# spi_mit_sram_v1.net
KiCad netlist of a schematic drawn in EAGLE
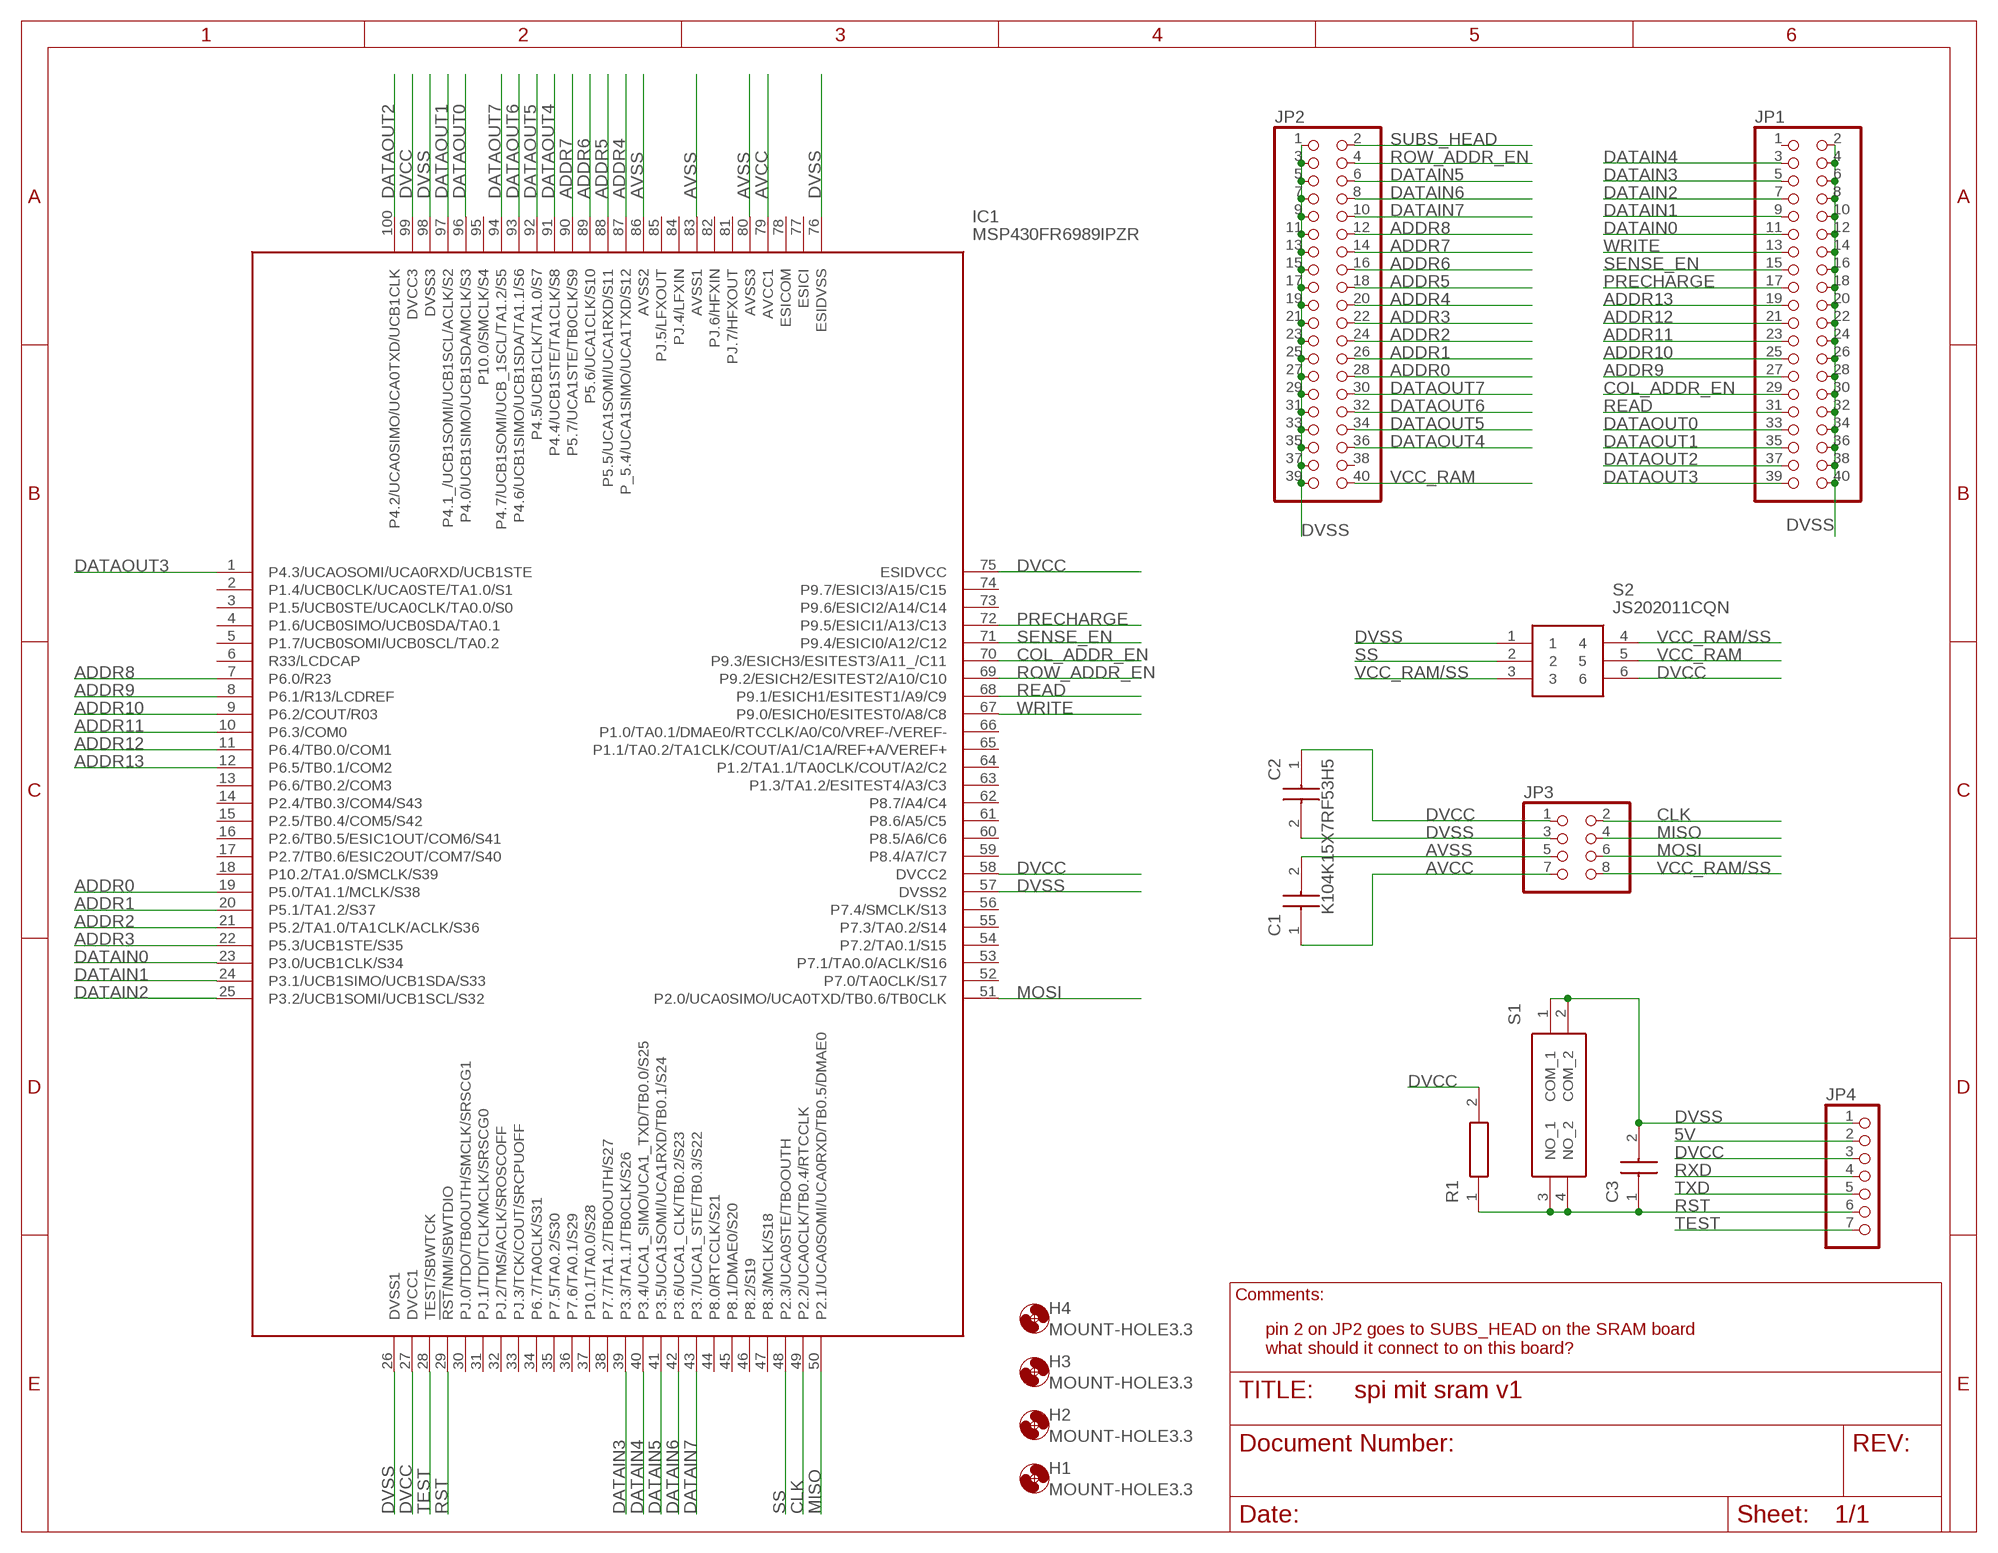
[diagram p0: schematic, sheet 1]

(export (version "E")
  (design (tool "Eeschema 10.0.6"))
  (components
    (comp (ref "C1")
      (value "K104K15X7RF53H5")
      (footprint "eagle-import:K104K15X7RF53H5")
      (fields
        (field (name "MOUSER_PART_NUMBER") "594-K104K15X7RF53H5")
        (field (name "RS_PART_NUMBER") "8523270")
      )
      (libsource (lib "eagle-import") (part "K104K15X7RF53H5"))
    )
    (comp (ref "C2")
      (value "K104K15X7RF53H5")
      (footprint "eagle-import:K104K15X7RF53H5")
      (fields
        (field (name "MOUSER_PART_NUMBER") "594-K104K15X7RF53H5")
        (field (name "RS_PART_NUMBER") "8523270")
      )
      (libsource (lib "eagle-import") (part "K104K15X7RF53H5"))
    )
    (comp (ref "C3")
      (value "K104K15X7RF53H5")
      (footprint "eagle-import:K104K15X7RF53H5")
      (fields
        (field (name "MOUSER_PART_NUMBER") "594-K104K15X7RF53H5")
        (field (name "RS_PART_NUMBER") "8523270")
      )
      (libsource (lib "eagle-import") (part "K104K15X7RF53H5"))
    )
    (comp (ref "H1")
      (value "MOUNT-HOLE3.3")
      (footprint "eagle-import:3,3")
      (libsource (lib "eagle-import") (part "MOUNT-HOLE3.3"))
    )
    (comp (ref "H2")
      (value "MOUNT-HOLE3.3")
      (footprint "eagle-import:3,3")
      (libsource (lib "eagle-import") (part "MOUNT-HOLE3.3"))
    )
    (comp (ref "H3")
      (value "MOUNT-HOLE3.3")
      (footprint "eagle-import:3,3")
      (libsource (lib "eagle-import") (part "MOUNT-HOLE3.3"))
    )
    (comp (ref "H4")
      (value "MOUNT-HOLE3.3")
      (footprint "eagle-import:3,3")
      (libsource (lib "eagle-import") (part "MOUNT-HOLE3.3"))
    )
    (comp (ref "IC1")
      (value "MSP430FR6989IPZR")
      (footprint "eagle-import:QFP50P1600X1600X160-100N")
      (fields (field (name "MOUSER_PART_NUMBER") "595-MSP430FR6989IPZR"))
      (libsource (lib "eagle-import") (part "MSP430FR6989IPZR"))
    )
    (comp (ref "JP1")
      (value "PINHD-2X20")
      (footprint "eagle-import:2X20")
      (libsource (lib "eagle-import") (part "PINHD-2X20"))
    )
    (comp (ref "JP2")
      (value "PINHD-2X20")
      (footprint "eagle-import:2X20")
      (libsource (lib "eagle-import") (part "PINHD-2X20"))
    )
    (comp (ref "JP3")
      (value "PINHD-2X4")
      (footprint "eagle-import:2X04")
      (libsource (lib "eagle-import") (part "PINHD-2X4"))
    )
    (comp (ref "JP4")
      (value "PINHD-1X7")
      (footprint "eagle-import:1X07")
      (libsource (lib "eagle-import") (part "PINHD-1X7"))
    )
    (comp (ref "R1")
      (value "MF0207FTE52-10K")
      (footprint "eagle-import:RESAD1590W60L630D240")
      (fields (field (name "MOUSER_PART_NUMBER") "603-MF0207FTE52-10K"))
      (libsource (lib "eagle-import") (part "MF0207FTE52-10K"))
    )
    (comp (ref "S1")
      (value "1825910-3")
      (footprint "eagle-import:18259103")
      (fields (field (name "RS_PART_NUMBER") "7455817P"))
      (libsource (lib "eagle-import") (part "1825910-3"))
    )
    (comp (ref "S2")
      (value "JS202011CQN")
      (footprint "eagle-import:JS202011CQN")
      (fields (field (name "MOUSER_PART_NUMBER") "611-JS202011CQN") (field (name "RS_PART_NUMBER") "1546136"))
      (libsource (lib "eagle-import") (part "JS202011CQN"))
    )
  )
  (nets
    (net (code "1") (name "/5V") (class "Default")
      (node (ref "JP4") (pin "2") (pinfunction "2_2") (pintype "passive"))
    )
    (net (code "2") (name "/ADDR0") (class "Default")
      (node (ref "IC1") (pin "19") (pinfunction "P5.0/TA1.1/MCLK/S38_19") (pintype "bidirectional"))
      (node (ref "JP2") (pin "28") (pinfunction "28_28") (pintype "passive"))
    )
    (net (code "3") (name "/ADDR1") (class "Default")
      (node (ref "IC1") (pin "20") (pinfunction "P5.1/TA1.2/S37_20") (pintype "bidirectional"))
      (node (ref "JP2") (pin "26") (pinfunction "26_26") (pintype "passive"))
    )
    (net (code "4") (name "/ADDR2") (class "Default")
      (node (ref "IC1") (pin "21") (pinfunction "P5.2/TA1.0/TA1CLK/ACLK/S36_21") (pintype "bidirectional"))
      (node (ref "JP2") (pin "24") (pinfunction "24_24") (pintype "passive"))
    )
    (net (code "5") (name "/ADDR3") (class "Default")
      (node (ref "IC1") (pin "22") (pinfunction "P5.3/UCB1STE/S35_22") (pintype "bidirectional"))
      (node (ref "JP2") (pin "22") (pinfunction "22_22") (pintype "passive"))
    )
    (net (code "6") (name "/ADDR4") (class "Default")
      (node (ref "IC1") (pin "87") (pinfunction "P_5.4/UCA1SIMO/UCA1TXD/S12_87") (pintype "bidirectional"))
      (node (ref "JP2") (pin "20") (pinfunction "20_20") (pintype "passive"))
    )
    (net (code "7") (name "/ADDR5") (class "Default")
      (node (ref "IC1") (pin "88") (pinfunction "P5.5/UCA1SOMI/UCA1RXD/S11_88") (pintype "bidirectional"))
      (node (ref "JP2") (pin "18") (pinfunction "18_18") (pintype "passive"))
    )
    (net (code "8") (name "/ADDR6") (class "Default")
      (node (ref "IC1") (pin "89") (pinfunction "P5.6/UCA1CLK/S10_89") (pintype "bidirectional"))
      (node (ref "JP2") (pin "16") (pinfunction "16_16") (pintype "passive"))
    )
    (net (code "9") (name "/ADDR7") (class "Default")
      (node (ref "IC1") (pin "90") (pinfunction "P5.7/UCA1STE/TB0CLK/S9_90") (pintype "bidirectional"))
      (node (ref "JP2") (pin "14") (pinfunction "14_14") (pintype "passive"))
    )
    (net (code "10") (name "/ADDR8") (class "Default")
      (node (ref "IC1") (pin "7") (pinfunction "P6.0/R23_7") (pintype "bidirectional"))
      (node (ref "JP2") (pin "12") (pinfunction "12_12") (pintype "passive"))
    )
    (net (code "11") (name "/ADDR9") (class "Default")
      (node (ref "IC1") (pin "8") (pinfunction "P6.1/R13/LCDREF_8") (pintype "bidirectional"))
      (node (ref "JP1") (pin "27") (pinfunction "27_27") (pintype "passive"))
    )
    (net (code "12") (name "/ADDR10") (class "Default")
      (node (ref "IC1") (pin "9") (pinfunction "P6.2/COUT/R03_9") (pintype "bidirectional"))
      (node (ref "JP1") (pin "25") (pinfunction "25_25") (pintype "passive"))
    )
    (net (code "13") (name "/ADDR11") (class "Default")
      (node (ref "IC1") (pin "10") (pinfunction "P6.3/COM0_10") (pintype "bidirectional"))
      (node (ref "JP1") (pin "23") (pinfunction "23_23") (pintype "passive"))
    )
    (net (code "14") (name "/ADDR12") (class "Default")
      (node (ref "IC1") (pin "11") (pinfunction "P6.4/TB0.0/COM1_11") (pintype "bidirectional"))
      (node (ref "JP1") (pin "21") (pinfunction "21_21") (pintype "passive"))
    )
    (net (code "15") (name "/ADDR13") (class "Default")
      (node (ref "IC1") (pin "12") (pinfunction "P6.5/TB0.1/COM2_12") (pintype "bidirectional"))
      (node (ref "JP1") (pin "19") (pinfunction "19_19") (pintype "passive"))
    )
    (net (code "16") (name "/AVCC") (class "Default")
      (node (ref "C1") (pin "1") (pinfunction "1_1") (pintype "bidirectional"))
      (node (ref "IC1") (pin "79") (pinfunction "AVCC1_79") (pintype "bidirectional"))
      (node (ref "JP3") (pin "7") (pinfunction "7_7") (pintype "passive"))
    )
    (net (code "17") (name "/AVSS") (class "Default")
      (node (ref "C1") (pin "2") (pinfunction "2_2") (pintype "bidirectional"))
      (node (ref "IC1") (pin "80") (pinfunction "AVSS3_80") (pintype "bidirectional"))
      (node (ref "IC1") (pin "83") (pinfunction "AVSS1_83") (pintype "bidirectional"))
      (node (ref "IC1") (pin "86") (pinfunction "AVSS2_86") (pintype "bidirectional"))
      (node (ref "JP3") (pin "5") (pinfunction "5_5") (pintype "passive"))
    )
    (net (code "18") (name "/CLK") (class "Default")
      (node (ref "IC1") (pin "49") (pinfunction "P2.2/UCA0CLK/TB0.4/RTCCLK_49") (pintype "bidirectional"))
      (node (ref "JP3") (pin "2") (pinfunction "2_2") (pintype "passive"))
    )
    (net (code "19") (name "/COL_ADDR_EN") (class "Default")
      (node (ref "IC1") (pin "70") (pinfunction "P9.3/ESICH3/ESITEST3/A11_/C11_70") (pintype "bidirectional"))
      (node (ref "JP1") (pin "29") (pinfunction "29_29") (pintype "passive"))
    )
    (net (code "20") (name "/DATAIN0") (class "Default")
      (node (ref "IC1") (pin "23") (pinfunction "P3.0/UCB1CLK/S34_23") (pintype "bidirectional"))
      (node (ref "JP1") (pin "11") (pinfunction "11_11") (pintype "passive"))
    )
    (net (code "21") (name "/DATAIN1") (class "Default")
      (node (ref "IC1") (pin "24") (pinfunction "P3.1/UCB1SIMO/UCB1SDA/S33_24") (pintype "bidirectional"))
      (node (ref "JP1") (pin "9") (pinfunction "9_9") (pintype "passive"))
    )
    (net (code "22") (name "/DATAIN2") (class "Default")
      (node (ref "IC1") (pin "25") (pinfunction "P3.2/UCB1SOMI/UCB1SCL/S32_25") (pintype "bidirectional"))
      (node (ref "JP1") (pin "7") (pinfunction "7_7") (pintype "passive"))
    )
    (net (code "23") (name "/DATAIN3") (class "Default")
      (node (ref "IC1") (pin "39") (pinfunction "P3.3/TA1.1/TB0CLK/S26_39") (pintype "bidirectional"))
      (node (ref "JP1") (pin "5") (pinfunction "5_5") (pintype "passive"))
    )
    (net (code "24") (name "/DATAIN4") (class "Default")
      (node (ref "IC1") (pin "40") (pinfunction "P3.4/UCA1_SIMO/UCA1_TXD/TB0.0/S25_40") (pintype "bidirectional"))
      (node (ref "JP1") (pin "3") (pinfunction "3_3") (pintype "passive"))
    )
    (net (code "25") (name "/DATAIN5") (class "Default")
      (node (ref "IC1") (pin "41") (pinfunction "P3.5/UCA1SOMI/UCA1RXD/TB0.1/S24_41") (pintype "bidirectional"))
      (node (ref "JP2") (pin "6") (pinfunction "6_6") (pintype "passive"))
    )
    (net (code "26") (name "/DATAIN6") (class "Default")
      (node (ref "IC1") (pin "42") (pinfunction "P3.6/UCA1_CLK/TB0.2/S23_42") (pintype "bidirectional"))
      (node (ref "JP2") (pin "8") (pinfunction "8_8") (pintype "passive"))
    )
    (net (code "27") (name "/DATAIN7") (class "Default")
      (node (ref "IC1") (pin "43") (pinfunction "P3.7/UCA1_STE/TB0.3/S22_43") (pintype "bidirectional"))
      (node (ref "JP2") (pin "10") (pinfunction "10_10") (pintype "passive"))
    )
    (net (code "28") (name "/DATAOUT0") (class "Default")
      (node (ref "IC1") (pin "96") (pinfunction "P4.0/UCB1SIMO/UCB1SDA/MCLK/S3_96") (pintype "bidirectional"))
      (node (ref "JP1") (pin "33") (pinfunction "33_33") (pintype "passive"))
    )
    (net (code "29") (name "/DATAOUT1") (class "Default")
      (node (ref "IC1") (pin "97") (pinfunction "P4.1_/UCB1SOMI/UCB1SCL/ACLK/S2_97") (pintype "bidirectional"))
      (node (ref "JP1") (pin "35") (pinfunction "35_35") (pintype "passive"))
    )
    (net (code "30") (name "/DATAOUT2") (class "Default")
      (node (ref "IC1") (pin "100") (pinfunction "P4.2/UCA0SIMO/UCA0TXD/UCB1CLK_100") (pintype "bidirectional"))
      (node (ref "JP1") (pin "37") (pinfunction "37_37") (pintype "passive"))
    )
    (net (code "31") (name "/DATAOUT3") (class "Default")
      (node (ref "IC1") (pin "1") (pinfunction "P4.3/UCAOSOMI/UCA0RXD/UCB1STE_1") (pintype "bidirectional"))
      (node (ref "JP1") (pin "39") (pinfunction "39_39") (pintype "passive"))
    )
    (net (code "32") (name "/DATAOUT4") (class "Default")
      (node (ref "IC1") (pin "91") (pinfunction "P4.4/UCB1STE/TA1CLK/S8_91") (pintype "bidirectional"))
      (node (ref "JP2") (pin "36") (pinfunction "36_36") (pintype "passive"))
    )
    (net (code "33") (name "/DATAOUT5") (class "Default")
      (node (ref "IC1") (pin "92") (pinfunction "P4.5/UCB1CLK/TA1.0/S7_92") (pintype "bidirectional"))
      (node (ref "JP2") (pin "34") (pinfunction "34_34") (pintype "passive"))
    )
    (net (code "34") (name "/DATAOUT6") (class "Default")
      (node (ref "IC1") (pin "93") (pinfunction "P4.6/UCB1SIMO/UCB1SDA/TA1.1/S6_93") (pintype "bidirectional"))
      (node (ref "JP2") (pin "32") (pinfunction "32_32") (pintype "passive"))
    )
    (net (code "35") (name "/DATAOUT7") (class "Default")
      (node (ref "IC1") (pin "94") (pinfunction "P4.7/UCB1SOMI/UCB_1SCL/TA1.2/S5_94") (pintype "bidirectional"))
      (node (ref "JP2") (pin "30") (pinfunction "30_30") (pintype "passive"))
    )
    (net (code "36") (name "/DVCC") (class "Default")
      (node (ref "C2") (pin "1") (pinfunction "1_1") (pintype "bidirectional"))
      (node (ref "IC1") (pin "27") (pinfunction "DVCC1_27") (pintype "bidirectional"))
      (node (ref "IC1") (pin "58") (pinfunction "DVCC2_58") (pintype "bidirectional"))
      (node (ref "IC1") (pin "75") (pinfunction "ESIDVCC_75") (pintype "bidirectional"))
      (node (ref "IC1") (pin "99") (pinfunction "DVCC3_99") (pintype "bidirectional"))
      (node (ref "JP3") (pin "1") (pinfunction "1_1") (pintype "passive"))
      (node (ref "JP4") (pin "3") (pinfunction "3_3") (pintype "passive"))
      (node (ref "R1") (pin "2") (pinfunction "2_2") (pintype "bidirectional"))
      (node (ref "S2") (pin "6") (pinfunction "6_6") (pintype "bidirectional"))
    )
    (net (code "37") (name "/DVSS") (class "Default")
      (node (ref "C2") (pin "2") (pinfunction "2_2") (pintype "bidirectional"))
      (node (ref "C3") (pin "2") (pinfunction "2_2") (pintype "bidirectional"))
      (node (ref "IC1") (pin "26") (pinfunction "DVSS1_26") (pintype "bidirectional"))
      (node (ref "IC1") (pin "57") (pinfunction "DVSS2_57") (pintype "bidirectional"))
      (node (ref "IC1") (pin "76") (pinfunction "ESIDVSS_76") (pintype "bidirectional"))
      (node (ref "IC1") (pin "98") (pinfunction "DVSS3_98") (pintype "bidirectional"))
      (node (ref "JP1") (pin "10") (pinfunction "10_10") (pintype "passive"))
      (node (ref "JP1") (pin "12") (pinfunction "12_12") (pintype "passive"))
      (node (ref "JP1") (pin "14") (pinfunction "14_14") (pintype "passive"))
      (node (ref "JP1") (pin "16") (pinfunction "16_16") (pintype "passive"))
      (node (ref "JP1") (pin "18") (pinfunction "18_18") (pintype "passive"))
      (node (ref "JP1") (pin "2") (pinfunction "2_2") (pintype "passive"))
      (node (ref "JP1") (pin "20") (pinfunction "20_20") (pintype "passive"))
      (node (ref "JP1") (pin "22") (pinfunction "22_22") (pintype "passive"))
      (node (ref "JP1") (pin "24") (pinfunction "24_24") (pintype "passive"))
      (node (ref "JP1") (pin "26") (pinfunction "26_26") (pintype "passive"))
      (node (ref "JP1") (pin "28") (pinfunction "28_28") (pintype "passive"))
      (node (ref "JP1") (pin "30") (pinfunction "30_30") (pintype "passive"))
      (node (ref "JP1") (pin "32") (pinfunction "32_32") (pintype "passive"))
      (node (ref "JP1") (pin "34") (pinfunction "34_34") (pintype "passive"))
      (node (ref "JP1") (pin "36") (pinfunction "36_36") (pintype "passive"))
      (node (ref "JP1") (pin "38") (pinfunction "38_38") (pintype "passive"))
      (node (ref "JP1") (pin "4") (pinfunction "4_4") (pintype "passive"))
      (node (ref "JP1") (pin "40") (pinfunction "40_40") (pintype "passive"))
      (node (ref "JP1") (pin "6") (pinfunction "6_6") (pintype "passive"))
      (node (ref "JP1") (pin "8") (pinfunction "8_8") (pintype "passive"))
      (node (ref "JP2") (pin "1") (pinfunction "1_1") (pintype "passive"))
      (node (ref "JP2") (pin "11") (pinfunction "11_11") (pintype "passive"))
      (node (ref "JP2") (pin "13") (pinfunction "13_13") (pintype "passive"))
      (node (ref "JP2") (pin "15") (pinfunction "15_15") (pintype "passive"))
      (node (ref "JP2") (pin "17") (pinfunction "17_17") (pintype "passive"))
      (node (ref "JP2") (pin "19") (pinfunction "19_19") (pintype "passive"))
      (node (ref "JP2") (pin "21") (pinfunction "21_21") (pintype "passive"))
      (node (ref "JP2") (pin "23") (pinfunction "23_23") (pintype "passive"))
      (node (ref "JP2") (pin "25") (pinfunction "25_25") (pintype "passive"))
      (node (ref "JP2") (pin "27") (pinfunction "27_27") (pintype "passive"))
      (node (ref "JP2") (pin "29") (pinfunction "29_29") (pintype "passive"))
      (node (ref "JP2") (pin "3") (pinfunction "3_3") (pintype "passive"))
      (node (ref "JP2") (pin "31") (pinfunction "31_31") (pintype "passive"))
      (node (ref "JP2") (pin "33") (pinfunction "33_33") (pintype "passive"))
      (node (ref "JP2") (pin "35") (pinfunction "35_35") (pintype "passive"))
      (node (ref "JP2") (pin "37") (pinfunction "37_37") (pintype "passive"))
      (node (ref "JP2") (pin "39") (pinfunction "39_39") (pintype "passive"))
      (node (ref "JP2") (pin "5") (pinfunction "5_5") (pintype "passive"))
      (node (ref "JP2") (pin "7") (pinfunction "7_7") (pintype "passive"))
      (node (ref "JP2") (pin "9") (pinfunction "9_9") (pintype "passive"))
      (node (ref "JP3") (pin "3") (pinfunction "3_3") (pintype "passive"))
      (node (ref "JP4") (pin "1") (pinfunction "1_1") (pintype "passive"))
      (node (ref "S1") (pin "1") (pinfunction "COM_1_1") (pintype "bidirectional"))
      (node (ref "S1") (pin "2") (pinfunction "COM_2_2") (pintype "bidirectional"))
      (node (ref "S2") (pin "1") (pinfunction "1_1") (pintype "bidirectional"))
    )
    (net (code "38") (name "/MISO") (class "Default")
      (node (ref "IC1") (pin "50") (pinfunction "P2.1/UCA0SOMI/UCA0RXD/TB0.5/DMAE0_50") (pintype "bidirectional"))
      (node (ref "JP3") (pin "4") (pinfunction "4_4") (pintype "passive"))
    )
    (net (code "39") (name "/MOSI") (class "Default")
      (node (ref "IC1") (pin "51") (pinfunction "P2.0/UCA0SIMO/UCA0TXD/TB0.6/TB0CLK_51") (pintype "bidirectional"))
      (node (ref "JP3") (pin "6") (pinfunction "6_6") (pintype "passive"))
    )
    (net (code "40") (name "/PRECHARGE") (class "Default")
      (node (ref "IC1") (pin "72") (pinfunction "P9.5/ESICI1/A13/C13_72") (pintype "bidirectional"))
      (node (ref "JP1") (pin "17") (pinfunction "17_17") (pintype "passive"))
    )
    (net (code "41") (name "/READ") (class "Default")
      (node (ref "IC1") (pin "68") (pinfunction "P9.1/ESICH1/ESITEST1/A9/C9_68") (pintype "bidirectional"))
      (node (ref "JP1") (pin "31") (pinfunction "31_31") (pintype "passive"))
    )
    (net (code "42") (name "/ROW_ADDR_EN") (class "Default")
      (node (ref "IC1") (pin "69") (pinfunction "P9.2/ESICH2/ESITEST2/A10/C10_69") (pintype "bidirectional"))
      (node (ref "JP2") (pin "4") (pinfunction "4_4") (pintype "passive"))
    )
    (net (code "43") (name "/RST") (class "Default")
      (node (ref "C3") (pin "1") (pinfunction "1_1") (pintype "bidirectional"))
      (node (ref "IC1") (pin "29") (pinfunction "~{RST}/NMI/SBWTDIO_29") (pintype "bidirectional"))
      (node (ref "JP4") (pin "6") (pinfunction "6_6") (pintype "passive"))
      (node (ref "R1") (pin "1") (pinfunction "1_1") (pintype "bidirectional"))
      (node (ref "S1") (pin "3") (pinfunction "NO_1_3") (pintype "bidirectional"))
      (node (ref "S1") (pin "4") (pinfunction "NO_2_4") (pintype "bidirectional"))
    )
    (net (code "44") (name "/RXD") (class "Default")
      (node (ref "JP4") (pin "4") (pinfunction "4_4") (pintype "passive"))
    )
    (net (code "45") (name "/SENSE_EN") (class "Default")
      (node (ref "IC1") (pin "71") (pinfunction "P9.4/ESICI0/A12/C12_71") (pintype "bidirectional"))
      (node (ref "JP1") (pin "15") (pinfunction "15_15") (pintype "passive"))
    )
    (net (code "46") (name "/SS") (class "Default")
      (node (ref "IC1") (pin "48") (pinfunction "P2.3/UCA0STE/TBOOUTH_48") (pintype "bidirectional"))
      (node (ref "S2") (pin "2") (pinfunction "2_2") (pintype "bidirectional"))
    )
    (net (code "47") (name "/SUBS_HEAD") (class "Default")
      (node (ref "JP2") (pin "2") (pinfunction "2_2") (pintype "passive"))
    )
    (net (code "48") (name "/TEST") (class "Default")
      (node (ref "IC1") (pin "28") (pinfunction "TEST/SBWTCK_28") (pintype "bidirectional"))
      (node (ref "JP4") (pin "7") (pinfunction "7_7") (pintype "passive"))
    )
    (net (code "49") (name "/TXD") (class "Default")
      (node (ref "JP4") (pin "5") (pinfunction "5_5") (pintype "passive"))
    )
    (net (code "50") (name "/VCC_RAM") (class "Default")
      (node (ref "JP2") (pin "40") (pinfunction "40_40") (pintype "passive"))
      (node (ref "S2") (pin "5") (pinfunction "5_5") (pintype "bidirectional"))
    )
    (net (code "51") (name "/VCC_RAM{slash}SS") (class "Default")
      (node (ref "JP3") (pin "8") (pinfunction "8_8") (pintype "passive"))
      (node (ref "S2") (pin "3") (pinfunction "3_3") (pintype "bidirectional"))
      (node (ref "S2") (pin "4") (pinfunction "4_4") (pintype "bidirectional"))
    )
    (net (code "52") (name "/WRITE") (class "Default")
      (node (ref "IC1") (pin "67") (pinfunction "P9.0/ESICH0/ESITEST0/A8/C8_67") (pintype "bidirectional"))
      (node (ref "JP1") (pin "13") (pinfunction "13_13") (pintype "passive"))
    )
    (net (code "53") (name "unconnected-(IC1-ESICI-Pad77)") (class "Default")
      (node (ref "IC1") (pin "77") (pinfunction "ESICI_77") (pintype "bidirectional"))
    )
    (net (code "54") (name "unconnected-(IC1-ESICOM-Pad78)") (class "Default")
      (node (ref "IC1") (pin "78") (pinfunction "ESICOM_78") (pintype "bidirectional"))
    )
    (net (code "55") (name "unconnected-(IC1-P1.0{slash}TA0.1{slash}DMAE0{slash}RTCCLK{slash}A0{slash}C0{slash}VREF-{slash}VEREF--Pad66)") (class "Default")
      (node (ref "IC1") (pin "66") (pinfunction "P1.0/TA0.1/DMAE0/RTCCLK/A0/C0/VREF-/VEREF-_66") (pintype "bidirectional"))
    )
    (net (code "56") (name "unconnected-(IC1-P1.1{slash}TA0.2{slash}TA1CLK{slash}COUT{slash}A1{slash}C1A{slash}REF+A{slash}VEREF+-Pad65)") (class "Default")
      (node (ref "IC1") (pin "65") (pinfunction "P1.1/TA0.2/TA1CLK/COUT/A1/C1A/REF+A/VEREF+_65") (pintype "bidirectional"))
    )
    (net (code "57") (name "unconnected-(IC1-P1.2{slash}TA1.1{slash}TA0CLK{slash}COUT{slash}A2{slash}C2-Pad64)") (class "Default")
      (node (ref "IC1") (pin "64") (pinfunction "P1.2/TA1.1/TA0CLK/COUT/A2/C2_64") (pintype "bidirectional"))
    )
    (net (code "58") (name "unconnected-(IC1-P1.3{slash}TA1.2{slash}ESITEST4{slash}A3{slash}C3-Pad63)") (class "Default")
      (node (ref "IC1") (pin "63") (pinfunction "P1.3/TA1.2/ESITEST4/A3/C3_63") (pintype "bidirectional"))
    )
    (net (code "59") (name "unconnected-(IC1-P1.4{slash}UCB0CLK{slash}UCA0STE{slash}TA1.0{slash}S1-Pad2)") (class "Default")
      (node (ref "IC1") (pin "2") (pinfunction "P1.4/UCB0CLK/UCA0STE/TA1.0/S1_2") (pintype "bidirectional"))
    )
    (net (code "60") (name "unconnected-(IC1-P1.5{slash}UCB0STE{slash}UCA0CLK{slash}TA0.0{slash}S0-Pad3)") (class "Default")
      (node (ref "IC1") (pin "3") (pinfunction "P1.5/UCB0STE/UCA0CLK/TA0.0/S0_3") (pintype "bidirectional"))
    )
    (net (code "61") (name "unconnected-(IC1-P1.6{slash}UCB0SIMO{slash}UCB0SDA{slash}TA0.1-Pad4)") (class "Default")
      (node (ref "IC1") (pin "4") (pinfunction "P1.6/UCB0SIMO/UCB0SDA/TA0.1_4") (pintype "bidirectional"))
    )
    (net (code "62") (name "unconnected-(IC1-P1.7{slash}UCB0SOMI{slash}UCB0SCL{slash}TA0.2-Pad5)") (class "Default")
      (node (ref "IC1") (pin "5") (pinfunction "P1.7/UCB0SOMI/UCB0SCL/TA0.2_5") (pintype "bidirectional"))
    )
    (net (code "63") (name "unconnected-(IC1-P2.4{slash}TB0.3{slash}COM4{slash}S43-Pad14)") (class "Default")
      (node (ref "IC1") (pin "14") (pinfunction "P2.4/TB0.3/COM4/S43_14") (pintype "bidirectional"))
    )
    (net (code "64") (name "unconnected-(IC1-P2.5{slash}TB0.4{slash}COM5{slash}S42-Pad15)") (class "Default")
      (node (ref "IC1") (pin "15") (pinfunction "P2.5/TB0.4/COM5/S42_15") (pintype "bidirectional"))
    )
    (net (code "65") (name "unconnected-(IC1-P2.6{slash}TB0.5{slash}ESIC1OUT{slash}COM6{slash}S41-Pad16)") (class "Default")
      (node (ref "IC1") (pin "16") (pinfunction "P2.6/TB0.5/ESIC1OUT/COM6/S41_16") (pintype "bidirectional"))
    )
    (net (code "66") (name "unconnected-(IC1-P2.7{slash}TB0.6{slash}ESIC2OUT{slash}COM7{slash}S40-Pad17)") (class "Default")
      (node (ref "IC1") (pin "17") (pinfunction "P2.7/TB0.6/ESIC2OUT/COM7/S40_17") (pintype "bidirectional"))
    )
    (net (code "67") (name "unconnected-(IC1-P6.6{slash}TB0.2{slash}COM3-Pad13)") (class "Default")
      (node (ref "IC1") (pin "13") (pinfunction "P6.6/TB0.2/COM3_13") (pintype "bidirectional"))
    )
    (net (code "68") (name "unconnected-(IC1-P6.7{slash}TA0CLK{slash}S31-Pad34)") (class "Default")
      (node (ref "IC1") (pin "34") (pinfunction "P6.7/TA0CLK/S31_34") (pintype "bidirectional"))
    )
    (net (code "69") (name "unconnected-(IC1-P7.0{slash}TA0CLK{slash}S17-Pad52)") (class "Default")
      (node (ref "IC1") (pin "52") (pinfunction "P7.0/TA0CLK/S17_52") (pintype "bidirectional"))
    )
    (net (code "70") (name "unconnected-(IC1-P7.1{slash}TA0.0{slash}ACLK{slash}S16-Pad53)") (class "Default")
      (node (ref "IC1") (pin "53") (pinfunction "P7.1/TA0.0/ACLK/S16_53") (pintype "bidirectional"))
    )
    (net (code "71") (name "unconnected-(IC1-P7.2{slash}TA0.1{slash}S15-Pad54)") (class "Default")
      (node (ref "IC1") (pin "54") (pinfunction "P7.2/TA0.1/S15_54") (pintype "bidirectional"))
    )
    (net (code "72") (name "unconnected-(IC1-P7.3{slash}TA0.2{slash}S14-Pad55)") (class "Default")
      (node (ref "IC1") (pin "55") (pinfunction "P7.3/TA0.2/S14_55") (pintype "bidirectional"))
    )
    (net (code "73") (name "unconnected-(IC1-P7.4{slash}SMCLK{slash}S13-Pad56)") (class "Default")
      (node (ref "IC1") (pin "56") (pinfunction "P7.4/SMCLK/S13_56") (pintype "bidirectional"))
    )
    (net (code "74") (name "unconnected-(IC1-P7.5{slash}TA0.2{slash}S30-Pad35)") (class "Default")
      (node (ref "IC1") (pin "35") (pinfunction "P7.5/TA0.2/S30_35") (pintype "bidirectional"))
    )
    (net (code "75") (name "unconnected-(IC1-P7.6{slash}TA0.1{slash}S29-Pad36)") (class "Default")
      (node (ref "IC1") (pin "36") (pinfunction "P7.6/TA0.1/S29_36") (pintype "bidirectional"))
    )
    (net (code "76") (name "unconnected-(IC1-P7.7{slash}TA1.2{slash}TB0OUTH{slash}S27-Pad38)") (class "Default")
      (node (ref "IC1") (pin "38") (pinfunction "P7.7/TA1.2/TB0OUTH/S27_38") (pintype "bidirectional"))
    )
    (net (code "77") (name "unconnected-(IC1-P8.0{slash}RTCCLK{slash}S21-Pad44)") (class "Default")
      (node (ref "IC1") (pin "44") (pinfunction "P8.0/RTCCLK/S21_44") (pintype "bidirectional"))
    )
    (net (code "78") (name "unconnected-(IC1-P8.1{slash}DMAE0{slash}S20-Pad45)") (class "Default")
      (node (ref "IC1") (pin "45") (pinfunction "P8.1/DMAE0/S20_45") (pintype "bidirectional"))
    )
    (net (code "79") (name "unconnected-(IC1-P8.2{slash}S19-Pad46)") (class "Default")
      (node (ref "IC1") (pin "46") (pinfunction "P8.2/S19_46") (pintype "bidirectional"))
    )
    (net (code "80") (name "unconnected-(IC1-P8.3{slash}MCLK{slash}S18-Pad47)") (class "Default")
      (node (ref "IC1") (pin "47") (pinfunction "P8.3/MCLK/S18_47") (pintype "bidirectional"))
    )
    (net (code "81") (name "unconnected-(IC1-P8.4{slash}A7{slash}C7-Pad59)") (class "Default")
      (node (ref "IC1") (pin "59") (pinfunction "P8.4/A7/C7_59") (pintype "bidirectional"))
    )
    (net (code "82") (name "unconnected-(IC1-P8.5{slash}A6{slash}C6-Pad60)") (class "Default")
      (node (ref "IC1") (pin "60") (pinfunction "P8.5/A6/C6_60") (pintype "bidirectional"))
    )
    (net (code "83") (name "unconnected-(IC1-P8.6{slash}A5{slash}C5-Pad61)") (class "Default")
      (node (ref "IC1") (pin "61") (pinfunction "P8.6/A5/C5_61") (pintype "bidirectional"))
    )
    (net (code "84") (name "unconnected-(IC1-P8.7{slash}A4{slash}C4-Pad62)") (class "Default")
      (node (ref "IC1") (pin "62") (pinfunction "P8.7/A4/C4_62") (pintype "bidirectional"))
    )
    (net (code "85") (name "unconnected-(IC1-P9.6{slash}ESICI2{slash}A14{slash}C14-Pad73)") (class "Default")
      (node (ref "IC1") (pin "73") (pinfunction "P9.6/ESICI2/A14/C14_73") (pintype "bidirectional"))
    )
    (net (code "86") (name "unconnected-(IC1-P9.7{slash}ESICI3{slash}A15{slash}C15-Pad74)") (class "Default")
      (node (ref "IC1") (pin "74") (pinfunction "P9.7/ESICI3/A15/C15_74") (pintype "bidirectional"))
    )
    (net (code "87") (name "unconnected-(IC1-P10.0{slash}SMCLK{slash}S4-Pad95)") (class "Default")
      (node (ref "IC1") (pin "95") (pinfunction "P10.0/SMCLK/S4_95") (pintype "bidirectional"))
    )
    (net (code "88") (name "unconnected-(IC1-P10.1{slash}TA0.0{slash}S28-Pad37)") (class "Default")
      (node (ref "IC1") (pin "37") (pinfunction "P10.1/TA0.0/S28_37") (pintype "bidirectional"))
    )
    (net (code "89") (name "unconnected-(IC1-P10.2{slash}TA1.0{slash}SMCLK{slash}S39-Pad18)") (class "Default")
      (node (ref "IC1") (pin "18") (pinfunction "P10.2/TA1.0/SMCLK/S39_18") (pintype "bidirectional"))
    )
    (net (code "90") (name "unconnected-(IC1-PJ.0{slash}TDO{slash}TB0OUTH{slash}SMCLK{slash}SRSCG1-Pad30)") (class "Default")
      (node (ref "IC1") (pin "30") (pinfunction "PJ.0/TDO/TB0OUTH/SMCLK/SRSCG1_30") (pintype "bidirectional"))
    )
    (net (code "91") (name "unconnected-(IC1-PJ.1{slash}TDI{slash}TCLK{slash}MCLK{slash}SRSCG0-Pad31)") (class "Default")
      (node (ref "IC1") (pin "31") (pinfunction "PJ.1/TDI/TCLK/MCLK/SRSCG0_31") (pintype "bidirectional"))
    )
    (net (code "92") (name "unconnected-(IC1-PJ.2{slash}TMS{slash}ACLK{slash}SROSCOFF-Pad32)") (class "Default")
      (node (ref "IC1") (pin "32") (pinfunction "PJ.2/TMS/ACLK/SROSCOFF_32") (pintype "bidirectional"))
    )
    (net (code "93") (name "unconnected-(IC1-PJ.3{slash}TCK{slash}COUT{slash}SRCPUOFF-Pad33)") (class "Default")
      (node (ref "IC1") (pin "33") (pinfunction "PJ.3/TCK/COUT/SRCPUOFF_33") (pintype "bidirectional"))
    )
    (net (code "94") (name "unconnected-(IC1-PJ.4{slash}LFXIN-Pad84)") (class "Default")
      (node (ref "IC1") (pin "84") (pinfunction "PJ.4/LFXIN_84") (pintype "bidirectional"))
    )
    (net (code "95") (name "unconnected-(IC1-PJ.5{slash}LFXOUT-Pad85)") (class "Default")
      (node (ref "IC1") (pin "85") (pinfunction "PJ.5/LFXOUT_85") (pintype "bidirectional"))
    )
    (net (code "96") (name "unconnected-(IC1-PJ.6{slash}HFXIN-Pad82)") (class "Default")
      (node (ref "IC1") (pin "82") (pinfunction "PJ.6/HFXIN_82") (pintype "bidirectional"))
    )
    (net (code "97") (name "unconnected-(IC1-PJ.7{slash}HFXOUT-Pad81)") (class "Default")
      (node (ref "IC1") (pin "81") (pinfunction "PJ.7/HFXOUT_81") (pintype "bidirectional"))
    )
    (net (code "98") (name "unconnected-(IC1-R33{slash}LCDCAP-Pad6)") (class "Default")
      (node (ref "IC1") (pin "6") (pinfunction "R33/LCDCAP_6") (pintype "bidirectional"))
    )
    (net (code "99") (name "unconnected-(JP1-Pad1)") (class "Default")
      (node (ref "JP1") (pin "1") (pinfunction "1_1") (pintype "passive"))
    )
    (net (code "100") (name "unconnected-(JP2-Pad38)") (class "Default")
      (node (ref "JP2") (pin "38") (pinfunction "38_38") (pintype "passive"))
    )
  )
)
